# egress.net
KiCad netlist of a schematic drawn in Altium Designer
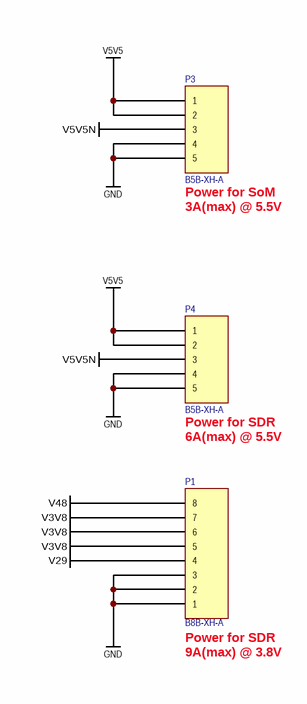
[diagram p0: egress.SchDoc]

(export (version "E")
  (design (tool "Eeschema 10.0.6"))
  (components
    (comp (ref "P1")
      (value "B8B-XH-A")
      (footprint "jst:B8B-XH-A")
      (description "2.5mm pitch 8-position connector")
      (fields (field (name "MANUFACTURER") "JST"))
      (libsource (lib "jst") (part "S8B-XH-A"))
    )
    (comp (ref "P3")
      (value "B5B-XH-A")
      (footprint "jst:B5B-XH-A")
      (description "2.5mm pitch 5-position connector")
      (fields (field (name "MANUFACTURER") "JST"))
      (libsource (lib "jst") (part "S5B-XH-A"))
    )
    (comp (ref "P4")
      (value "B5B-XH-A")
      (footprint "jst:B5B-XH-A")
      (description "2.5mm pitch 5-position connector")
      (fields (field (name "MANUFACTURER") "JST"))
      (libsource (lib "jst") (part "S5B-XH-A"))
    )
  )
  (nets
    (net (code "1") (name "GND") (class "Default")
      (node (ref "P1") (pin "1") (pinfunction "1_1") (pintype "passive"))
      (node (ref "P1") (pin "2") (pinfunction "2_2") (pintype "passive"))
      (node (ref "P1") (pin "3") (pinfunction "3_3") (pintype "passive"))
      (node (ref "P3") (pin "4") (pinfunction "4_4") (pintype "passive"))
      (node (ref "P3") (pin "5") (pinfunction "5_5") (pintype "passive"))
      (node (ref "P4") (pin "4") (pinfunction "4_4") (pintype "passive"))
      (node (ref "P4") (pin "5") (pinfunction "5_5") (pintype "passive"))
    )
    (net (code "2") (name "V3V8") (class "Default")
      (node (ref "P1") (pin "5") (pinfunction "5_5") (pintype "passive"))
      (node (ref "P1") (pin "6") (pinfunction "6_6") (pintype "passive"))
      (node (ref "P1") (pin "7") (pinfunction "7_7") (pintype "passive"))
    )
    (net (code "3") (name "V5V5") (class "Default")
      (node (ref "P3") (pin "1") (pinfunction "1_1") (pintype "passive"))
      (node (ref "P3") (pin "2") (pinfunction "2_2") (pintype "passive"))
      (node (ref "P4") (pin "1") (pinfunction "1_1") (pintype "passive"))
      (node (ref "P4") (pin "2") (pinfunction "2_2") (pintype "passive"))
    )
    (net (code "4") (name "V5V5N") (class "Default")
      (node (ref "P3") (pin "3") (pinfunction "3_3") (pintype "passive"))
      (node (ref "P4") (pin "3") (pinfunction "3_3") (pintype "passive"))
    )
    (net (code "5") (name "V29") (class "Default")
      (node (ref "P1") (pin "4") (pinfunction "4_4") (pintype "passive"))
    )
    (net (code "6") (name "V48") (class "Default")
      (node (ref "P1") (pin "8") (pinfunction "8_8") (pintype "passive"))
    )
  )
)
